# 10-Buffer.net
KiCad netlist of a schematic drawn in Altium Designer
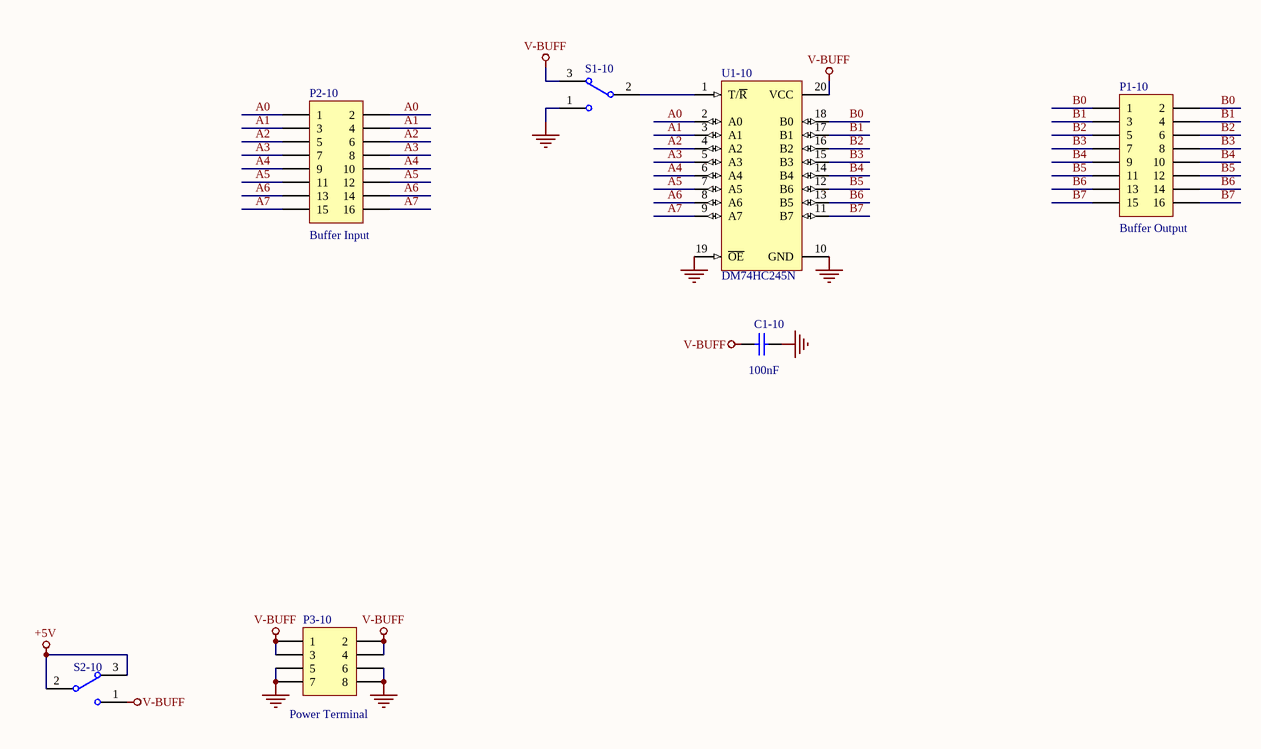
[diagram p0: 10-Buffer.SchDoc]

(export (version "E")
  (design (tool "Eeschema 10.0.6"))
  (components
    (comp (ref "C1-10")
      (value "100nF")
      (footprint "c-0805")
      (description "Capacitor")
      (fields (field (name "Comment") "104") (field (name "PUBLISHER") "Altium Limited"))
      (libsource (lib "Miscellaneous Devices") (part "Cap"))
    )
    (comp (ref "P1-10")
      (value "Buffer Output")
      (footprint "JP2.54-F-2x08A")
      (description "Header, 8-Pin, Dual row")
      (fields (field (name "Comment") "Header 8X2"))
      (libsource (lib "Miscellaneous Connectors") (part "Header 8X2"))
    )
    (comp (ref "P2-10")
      (value "Buffer Input")
      (footprint "JP2.54-F-2x08A")
      (description "Header, 8-Pin, Dual row")
      (fields (field (name "Comment") "Header 8X2"))
      (libsource (lib "Miscellaneous Connectors") (part "Header 8X2"))
    )
    (comp (ref "P3-10")
      (value "Header 4X2")
      (footprint "JP2.54-F-2x04A")
      (description "Header, 4-Pin, Dual row")
      (fields (field (name "PUBLISHER") "Power Terminal"))
      (libsource (lib "Miscellaneous Connectors") (part "Header 4X2"))
    )
    (comp (ref "S1-10")
      (value "SW-SPDT")
      (footprint "SW-SLIDE-2P-2W")
      (description "SPDT Subminiature Toggle Switch, Right Angle Mounting, Vertical Actuation")
      (fields (field (name "PUBLISHER") "Altium Limited"))
      (libsource (lib "Miscellaneous Devices") (part "SW-SPDT"))
    )
    (comp (ref "S2-10")
      (value "SW-SPDT")
      (footprint "SW-SLIDE-2P-2W")
      (description "SPDT Subminiature Toggle Switch, Right Angle Mounting, Vertical Actuation")
      (fields (field (name "PUBLISHER") "Altium Limited"))
      (libsource (lib "Miscellaneous Devices") (part "SW-SPDT"))
    )
    (comp (ref "U1-10")
      (value "DM74HC245N")
      (footprint "SK-DIP20-300")
      (description "3-State Octal Bus Transceiver")
      (fields (field (name "PUBLISHER") "Altium Limited"))
      (libsource (lib "FSC Interface Line Transceiver") (part "DM74LS245N"))
    )
  )
  (nets
    (net (code "1") (name "+5V") (class "Default")
      (node (ref "S2-10") (pin "2") (pinfunction "2_2") (pintype "passive"))
      (node (ref "S2-10") (pin "3") (pinfunction "3_3") (pintype "passive"))
    )
    (net (code "2") (name "/A0") (class "Default")
      (node (ref "P2-10") (pin "1") (pinfunction "1_1") (pintype "passive"))
      (node (ref "P2-10") (pin "2") (pinfunction "2_2") (pintype "passive"))
      (node (ref "U1-10") (pin "2") (pinfunction "A0_2") (pintype "bidirectional"))
    )
    (net (code "3") (name "/A1") (class "Default")
      (node (ref "P2-10") (pin "3") (pinfunction "3_3") (pintype "passive"))
      (node (ref "P2-10") (pin "4") (pinfunction "4_4") (pintype "passive"))
      (node (ref "U1-10") (pin "3") (pinfunction "A1_3") (pintype "bidirectional"))
    )
    (net (code "4") (name "/A2") (class "Default")
      (node (ref "P2-10") (pin "5") (pinfunction "5_5") (pintype "passive"))
      (node (ref "P2-10") (pin "6") (pinfunction "6_6") (pintype "passive"))
      (node (ref "U1-10") (pin "4") (pinfunction "A2_4") (pintype "bidirectional"))
    )
    (net (code "5") (name "/A3") (class "Default")
      (node (ref "P2-10") (pin "7") (pinfunction "7_7") (pintype "passive"))
      (node (ref "P2-10") (pin "8") (pinfunction "8_8") (pintype "passive"))
      (node (ref "U1-10") (pin "5") (pinfunction "A3_5") (pintype "bidirectional"))
    )
    (net (code "6") (name "/A4") (class "Default")
      (node (ref "P2-10") (pin "10") (pinfunction "10_10") (pintype "passive"))
      (node (ref "P2-10") (pin "9") (pinfunction "9_9") (pintype "passive"))
      (node (ref "U1-10") (pin "6") (pinfunction "A4_6") (pintype "bidirectional"))
    )
    (net (code "7") (name "/A5") (class "Default")
      (node (ref "P2-10") (pin "11") (pinfunction "11_11") (pintype "passive"))
      (node (ref "P2-10") (pin "12") (pinfunction "12_12") (pintype "passive"))
      (node (ref "U1-10") (pin "7") (pinfunction "A5_7") (pintype "bidirectional"))
    )
    (net (code "8") (name "/A6") (class "Default")
      (node (ref "P2-10") (pin "13") (pinfunction "13_13") (pintype "passive"))
      (node (ref "P2-10") (pin "14") (pinfunction "14_14") (pintype "passive"))
      (node (ref "U1-10") (pin "8") (pinfunction "A6_8") (pintype "bidirectional"))
    )
    (net (code "9") (name "/A7") (class "Default")
      (node (ref "P2-10") (pin "15") (pinfunction "15_15") (pintype "passive"))
      (node (ref "P2-10") (pin "16") (pinfunction "16_16") (pintype "passive"))
      (node (ref "U1-10") (pin "9") (pinfunction "A7_9") (pintype "bidirectional"))
    )
    (net (code "10") (name "/B0") (class "Default")
      (node (ref "P1-10") (pin "1") (pinfunction "1_1") (pintype "passive"))
      (node (ref "P1-10") (pin "2") (pinfunction "2_2") (pintype "passive"))
      (node (ref "U1-10") (pin "18") (pinfunction "B0_18") (pintype "bidirectional"))
    )
    (net (code "11") (name "/B1") (class "Default")
      (node (ref "P1-10") (pin "3") (pinfunction "3_3") (pintype "passive"))
      (node (ref "P1-10") (pin "4") (pinfunction "4_4") (pintype "passive"))
      (node (ref "U1-10") (pin "17") (pinfunction "B1_17") (pintype "bidirectional"))
    )
    (net (code "12") (name "/B2") (class "Default")
      (node (ref "P1-10") (pin "5") (pinfunction "5_5") (pintype "passive"))
      (node (ref "P1-10") (pin "6") (pinfunction "6_6") (pintype "passive"))
      (node (ref "U1-10") (pin "16") (pinfunction "B2_16") (pintype "bidirectional"))
    )
    (net (code "13") (name "/B3") (class "Default")
      (node (ref "P1-10") (pin "7") (pinfunction "7_7") (pintype "passive"))
      (node (ref "P1-10") (pin "8") (pinfunction "8_8") (pintype "passive"))
      (node (ref "U1-10") (pin "15") (pinfunction "B3_15") (pintype "bidirectional"))
    )
    (net (code "14") (name "/B4") (class "Default")
      (node (ref "P1-10") (pin "10") (pinfunction "10_10") (pintype "passive"))
      (node (ref "P1-10") (pin "9") (pinfunction "9_9") (pintype "passive"))
      (node (ref "U1-10") (pin "14") (pinfunction "B4_14") (pintype "bidirectional"))
    )
    (net (code "15") (name "/B5") (class "Default")
      (node (ref "P1-10") (pin "11") (pinfunction "11_11") (pintype "passive"))
      (node (ref "P1-10") (pin "12") (pinfunction "12_12") (pintype "passive"))
      (node (ref "U1-10") (pin "12") (pinfunction "B6_12") (pintype "bidirectional"))
    )
    (net (code "16") (name "/B6") (class "Default")
      (node (ref "P1-10") (pin "13") (pinfunction "13_13") (pintype "passive"))
      (node (ref "P1-10") (pin "14") (pinfunction "14_14") (pintype "passive"))
      (node (ref "U1-10") (pin "13") (pinfunction "B5_13") (pintype "bidirectional"))
    )
    (net (code "17") (name "/B7") (class "Default")
      (node (ref "P1-10") (pin "15") (pinfunction "15_15") (pintype "passive"))
      (node (ref "P1-10") (pin "16") (pinfunction "16_16") (pintype "passive"))
      (node (ref "U1-10") (pin "11") (pinfunction "B7_11") (pintype "bidirectional"))
    )
    (net (code "18") (name "GND") (class "Default")
      (node (ref "C1-10") (pin "2") (pinfunction "2_2") (pintype "passive"))
      (node (ref "P3-10") (pin "5") (pinfunction "5_5") (pintype "passive"))
      (node (ref "P3-10") (pin "6") (pinfunction "6_6") (pintype "passive"))
      (node (ref "P3-10") (pin "7") (pinfunction "7_7") (pintype "passive"))
      (node (ref "P3-10") (pin "8") (pinfunction "8_8") (pintype "passive"))
      (node (ref "S1-10") (pin "1") (pinfunction "1_1") (pintype "passive"))
      (node (ref "U1-10") (pin "10") (pinfunction "GND_10") (pintype "power_in"))
      (node (ref "U1-10") (pin "19") (pinfunction "~{OE}_19") (pintype "input"))
    )
    (net (code "19") (name "Net-(U1-10-T{slash}~{R})") (class "Default")
      (node (ref "S1-10") (pin "2") (pinfunction "2_2") (pintype "passive"))
      (node (ref "U1-10") (pin "1") (pinfunction "T/~{R}_1") (pintype "input"))
    )
    (net (code "20") (name "V-BUFF") (class "Default")
      (node (ref "C1-10") (pin "1") (pinfunction "1_1") (pintype "passive"))
      (node (ref "P3-10") (pin "1") (pinfunction "1_1") (pintype "passive"))
      (node (ref "P3-10") (pin "2") (pinfunction "2_2") (pintype "passive"))
      (node (ref "P3-10") (pin "3") (pinfunction "3_3") (pintype "passive"))
      (node (ref "P3-10") (pin "4") (pinfunction "4_4") (pintype "passive"))
      (node (ref "S1-10") (pin "3") (pinfunction "3_3") (pintype "passive"))
      (node (ref "S2-10") (pin "1") (pinfunction "1_1") (pintype "passive"))
      (node (ref "U1-10") (pin "20") (pinfunction "VCC_20") (pintype "power_in"))
    )
  )
)
